# Motor_Driver.net
KiCad netlist of a schematic drawn in Altium Designer
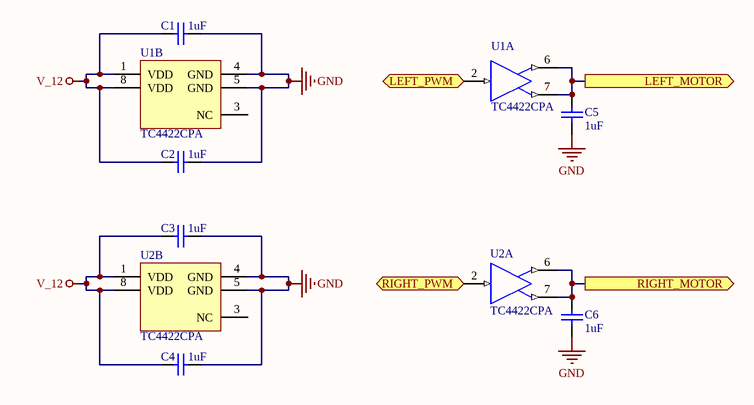
[diagram p0: Motor_Driver.SchDoc]

(export (version "E")
  (design (tool "Eeschema 10.0.6"))
  (components
    (comp (ref "C1")
      (value "1uF")
      (footprint "RAD-0.3")
      (description "Capacitor")
      (fields (field (name "Comment") "Cap") (field (name "PUBLISHER") "Altium Limited"))
      (libsource (lib "Miscellaneous Devices") (part "Cap"))
    )
    (comp (ref "C2")
      (value "1uF")
      (footprint "RAD-0.3")
      (description "Capacitor")
      (fields (field (name "Comment") "Cap") (field (name "PUBLISHER") "Altium Limited"))
      (libsource (lib "Miscellaneous Devices") (part "Cap"))
    )
    (comp (ref "C3")
      (value "1uF")
      (footprint "RAD-0.3")
      (description "Capacitor")
      (fields (field (name "Comment") "Cap") (field (name "PUBLISHER") "Altium Limited"))
      (libsource (lib "Miscellaneous Devices") (part "Cap"))
    )
    (comp (ref "C4")
      (value "1uF")
      (footprint "RAD-0.3")
      (description "Capacitor")
      (fields (field (name "Comment") "Cap") (field (name "PUBLISHER") "Altium Limited"))
      (libsource (lib "Miscellaneous Devices") (part "Cap"))
    )
    (comp (ref "C5")
      (value "1uF")
      (footprint "RAD-0.3")
      (description "Capacitor")
      (fields (field (name "Comment") "Cap") (field (name "PUBLISHER") "Altium Limited"))
      (libsource (lib "Miscellaneous Devices") (part "Cap"))
    )
    (comp (ref "C6")
      (value "1uF")
      (footprint "RAD-0.3")
      (description "Capacitor")
      (fields (field (name "Comment") "Cap") (field (name "PUBLISHER") "Altium Limited"))
      (libsource (lib "Miscellaneous Devices") (part "Cap"))
    )
    (comp (ref "U1")
      (value "TC4422CPA")
      (footprint "PDIP300-PA8")
      (description "9A High-Speed MOSFET Driver, Non-Inverting, Commercial Temperature")
      (fields (field (name "PUBLISHER") "Altium Limited"))
      (libsource (lib "Microchip Power Mgt MOSFET Driver") (part "TC4422CPA"))
    )
    (comp (ref "U2")
      (value "TC4422CPA")
      (footprint "PDIP300-PA8")
      (description "9A High-Speed MOSFET Driver, Non-Inverting, Commercial Temperature")
      (fields (field (name "PUBLISHER") "Altium Limited"))
      (libsource (lib "Microchip Power Mgt MOSFET Driver") (part "TC4422CPA"))
    )
  )
  (nets
    (net (code "1") (name "/LEFT_MOTOR") (class "Default")
      (node (ref "C5") (pin "2") (pinfunction "2_2") (pintype "passive"))
      (node (ref "U1") (pin "6") (pinfunction "OUT_6") (pintype "output"))
      (node (ref "U1") (pin "7") (pinfunction "OUT_7") (pintype "output"))
    )
    (net (code "2") (name "/LEFT_PWM") (class "Default")
      (node (ref "U1") (pin "2") (pinfunction "IN_2") (pintype "input"))
    )
    (net (code "3") (name "/RIGHT_MOTOR") (class "Default")
      (node (ref "C6") (pin "2") (pinfunction "2_2") (pintype "passive"))
      (node (ref "U2") (pin "6") (pinfunction "OUT_6") (pintype "output"))
      (node (ref "U2") (pin "7") (pinfunction "OUT_7") (pintype "output"))
    )
    (net (code "4") (name "/RIGHT_PWM") (class "Default")
      (node (ref "U2") (pin "2") (pinfunction "IN_2") (pintype "input"))
    )
    (net (code "5") (name "GND") (class "Default")
      (node (ref "C1") (pin "2") (pinfunction "2_2") (pintype "passive"))
      (node (ref "C2") (pin "2") (pinfunction "2_2") (pintype "passive"))
      (node (ref "C3") (pin "2") (pinfunction "2_2") (pintype "passive"))
      (node (ref "C4") (pin "2") (pinfunction "2_2") (pintype "passive"))
      (node (ref "C5") (pin "1") (pinfunction "1_1") (pintype "passive"))
      (node (ref "C6") (pin "1") (pinfunction "1_1") (pintype "passive"))
      (node (ref "U1") (pin "4") (pinfunction "GND_4") (pintype "power_in"))
      (node (ref "U1") (pin "5") (pinfunction "GND_5") (pintype "power_in"))
      (node (ref "U2") (pin "4") (pinfunction "GND_4") (pintype "power_in"))
      (node (ref "U2") (pin "5") (pinfunction "GND_5") (pintype "power_in"))
    )
    (net (code "6") (name "V_12") (class "Default")
      (node (ref "C1") (pin "1") (pinfunction "1_1") (pintype "passive"))
      (node (ref "C2") (pin "1") (pinfunction "1_1") (pintype "passive"))
      (node (ref "C3") (pin "1") (pinfunction "1_1") (pintype "passive"))
      (node (ref "C4") (pin "1") (pinfunction "1_1") (pintype "passive"))
      (node (ref "U1") (pin "1") (pinfunction "VDD_1") (pintype "power_in"))
      (node (ref "U1") (pin "8") (pinfunction "VDD_8") (pintype "power_in"))
      (node (ref "U2") (pin "1") (pinfunction "VDD_1") (pintype "power_in"))
      (node (ref "U2") (pin "8") (pinfunction "VDD_8") (pintype "power_in"))
    )
    (net (code "7") (name "unconnected-(U1B-NC-Pad3)") (class "Default")
      (node (ref "U1") (pin "3") (pinfunction "NC_3") (pintype "passive"))
    )
    (net (code "8") (name "unconnected-(U2B-NC-Pad3)") (class "Default")
      (node (ref "U2") (pin "3") (pinfunction "NC_3") (pintype "passive"))
    )
  )
)
